# Radio.net
KiCad netlist of a schematic drawn in Altium Designer
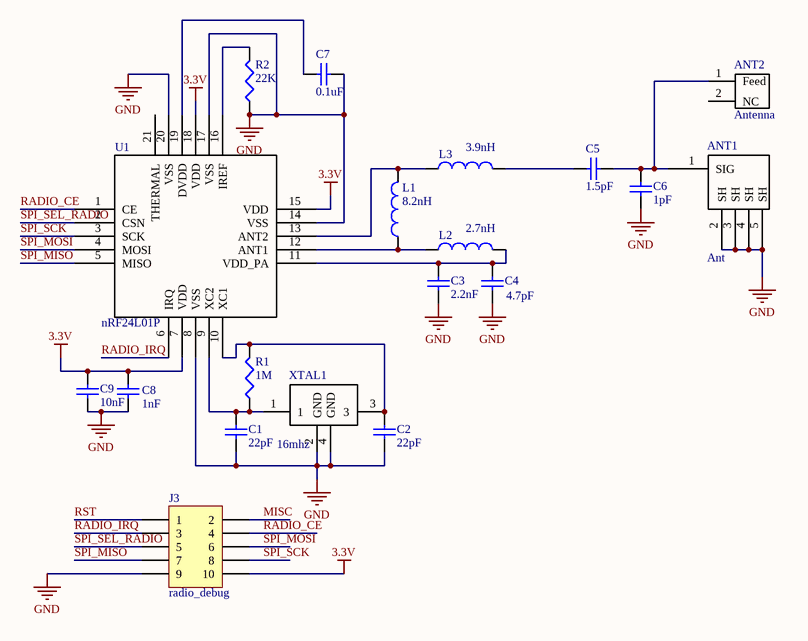
[diagram p0: Radio.SchDoc]

(export (version "E")
  (design (tool "Eeschema 10.0.6"))
  (components
    (comp (ref "ANT1") (value "Ant") (footprint "AntennaSMA") (libsource (lib "mrone") (part "AntennaConn")))
    (comp (ref "ANT2") (value "Antenna") (footprint "antenna") (libsource (lib "mrone") (part "Antenna")))
    (comp (ref "C1")
      (value "22pF")
      (footprint "CAPC1005L")
      (description "Capacitor (Semiconductor SIM Model)")
      (fields (field (name "Comment") "Cap Semi") (field (name "PUBLISHER") "Altium Limited"))
      (libsource (lib "Miscellaneous Devices") (part "Cap Semi"))
    )
    (comp (ref "C2")
      (value "22pF")
      (footprint "CAPC1005L")
      (description "Capacitor (Semiconductor SIM Model)")
      (fields (field (name "Comment") "Cap Semi") (field (name "PUBLISHER") "Altium Limited"))
      (libsource (lib "Miscellaneous Devices") (part "Cap Semi"))
    )
    (comp (ref "C3")
      (value "2.2nF")
      (footprint "CAPC1005L")
      (description "Capacitor (Semiconductor SIM Model)")
      (fields (field (name "Comment") "Cap Semi") (field (name "PUBLISHER") "Altium Limited"))
      (libsource (lib "Miscellaneous Devices") (part "Cap Semi"))
    )
    (comp (ref "C4")
      (value "4.7pF")
      (footprint "CAPC1005L")
      (description "Capacitor (Semiconductor SIM Model)")
      (fields (field (name "Comment") "Cap Semi") (field (name "PUBLISHER") "Altium Limited"))
      (libsource (lib "Miscellaneous Devices") (part "Cap Semi"))
    )
    (comp (ref "C5")
      (value "1.5pF")
      (footprint "CAPC1005L")
      (description "Capacitor (Semiconductor SIM Model)")
      (fields (field (name "Comment") "Cap Semi") (field (name "PUBLISHER") "Altium Limited"))
      (libsource (lib "Miscellaneous Devices") (part "Cap Semi"))
    )
    (comp (ref "C6")
      (value "1pF")
      (footprint "CAPC1005L")
      (description "Capacitor (Semiconductor SIM Model)")
      (fields (field (name "Comment") "Cap Semi") (field (name "PUBLISHER") "Altium Limited"))
      (libsource (lib "Miscellaneous Devices") (part "Cap Semi"))
    )
    (comp (ref "C7")
      (value "0.1uF")
      (footprint "CAPC1005L")
      (description "Capacitor (Semiconductor SIM Model)")
      (fields (field (name "Comment") "Cap Semi") (field (name "PUBLISHER") "Altium Limited"))
      (libsource (lib "Miscellaneous Devices") (part "Cap Semi"))
    )
    (comp (ref "C8")
      (value "1nF")
      (footprint "CAPC1005L")
      (description "Capacitor (Semiconductor SIM Model)")
      (fields (field (name "Comment") "Cap Semi") (field (name "PUBLISHER") "Altium Limited"))
      (libsource (lib "Miscellaneous Devices") (part "Cap Semi"))
    )
    (comp (ref "C9")
      (value "10nF")
      (footprint "CAPC1005L")
      (description "Capacitor (Semiconductor SIM Model)")
      (fields (field (name "Comment") "Cap Semi") (field (name "PUBLISHER") "Altium Limited"))
      (libsource (lib "Miscellaneous Devices") (part "Cap Semi"))
    )
    (comp (ref "J3")
      (value "radio_debug")
      (footprint "HDR2X5")
      (description "Header, 5-Pin, Dual row")
      (fields (field (name "PUBLISHER") "Altium Limited"))
      (libsource (lib "Miscellaneous Connectors") (part "Header 5X2"))
    )
    (comp (ref "L1")
      (value "8.2nH")
      (footprint "INDC1005AL")
      (description "Inductor")
      (fields (field (name "PUBLISHER") "Altium Limited"))
      (libsource (lib "Miscellaneous Devices") (part "Inductor"))
    )
    (comp (ref "L2")
      (value "2.7nH")
      (footprint "INDC1005AL")
      (description "Inductor")
      (fields (field (name "PUBLISHER") "Altium Limited"))
      (libsource (lib "Miscellaneous Devices") (part "Inductor"))
    )
    (comp (ref "L3")
      (value "3.9nH")
      (footprint "INDC1005AL")
      (description "Inductor")
      (fields (field (name "PUBLISHER") "Altium Limited"))
      (libsource (lib "Miscellaneous Devices") (part "Inductor"))
    )
    (comp (ref "R1")
      (value "1M")
      (footprint "RESC1608L")
      (description "Resistor")
      (fields (field (name "Comment") "Res3") (field (name "PUBLISHER") "Altium Limited"))
      (libsource (lib "Miscellaneous Devices") (part "Res3"))
    )
    (comp (ref "R2")
      (value "22K")
      (footprint "RESC1608L")
      (description "Resistor")
      (fields (field (name "Comment") "Res3") (field (name "PUBLISHER") "Altium Limited"))
      (libsource (lib "Miscellaneous Devices") (part "Res3"))
    )
    (comp (ref "U1")
      (value "nRF24L01P")
      (footprint "QFN-20")
      (libsource (lib "mrone") (part "radio-nRF24L01P"))
    )
    (comp (ref "XTAL1")
      (value "16mhz")
      (footprint "RadioCrystal")
      (fields (field (name "Comment") "RADIO CRYSTAL"))
      (libsource (lib "Schematic Components") (part "RadioCrystal"))
    )
  )
  (nets
    (net (code "1") (name "/MISC") (class "Default")
      (node (ref "J3") (pin "2") (pinfunction "2_2") (pintype "passive"))
    )
    (net (code "2") (name "/RADIO_CE") (class "Default")
      (node (ref "J3") (pin "4") (pinfunction "4_4") (pintype "passive"))
      (node (ref "U1") (pin "1") (pinfunction "CE_1") (pintype "passive"))
    )
    (net (code "3") (name "/RADIO_IRQ") (class "Default")
      (node (ref "J3") (pin "3") (pinfunction "3_3") (pintype "passive"))
      (node (ref "U1") (pin "6") (pinfunction "IRQ_6") (pintype "passive"))
    )
    (net (code "4") (name "/RST") (class "Default")
      (node (ref "J3") (pin "1") (pinfunction "1_1") (pintype "passive"))
    )
    (net (code "5") (name "/SPI_MISO") (class "Default")
      (node (ref "J3") (pin "7") (pinfunction "7_7") (pintype "passive"))
      (node (ref "U1") (pin "5") (pinfunction "MISO_5") (pintype "passive"))
    )
    (net (code "6") (name "/SPI_MOSI") (class "Default")
      (node (ref "J3") (pin "6") (pinfunction "6_6") (pintype "passive"))
      (node (ref "U1") (pin "4") (pinfunction "MOSI_4") (pintype "passive"))
    )
    (net (code "7") (name "/SPI_SCK") (class "Default")
      (node (ref "J3") (pin "8") (pinfunction "8_8") (pintype "passive"))
      (node (ref "U1") (pin "3") (pinfunction "SCK_3") (pintype "passive"))
    )
    (net (code "8") (name "/SPI_SEL_RADIO") (class "Default")
      (node (ref "J3") (pin "5") (pinfunction "5_5") (pintype "passive"))
      (node (ref "U1") (pin "2") (pinfunction "CSN_2") (pintype "passive"))
    )
    (net (code "9") (name "3.3V") (class "Default")
      (node (ref "C8") (pin "2") (pinfunction "2_2") (pintype "passive"))
      (node (ref "C9") (pin "2") (pinfunction "2_2") (pintype "passive"))
      (node (ref "J3") (pin "10") (pinfunction "10_10") (pintype "passive"))
      (node (ref "U1") (pin "15") (pinfunction "VDD_15") (pintype "passive"))
      (node (ref "U1") (pin "18") (pinfunction "VDD_18") (pintype "passive"))
      (node (ref "U1") (pin "7") (pinfunction "VDD_7") (pintype "passive"))
    )
    (net (code "10") (name "GND") (class "Default")
      (node (ref "ANT1") (pin "2") (pinfunction "SH_2") (pintype "passive"))
      (node (ref "ANT1") (pin "3") (pinfunction "SH_3") (pintype "passive"))
      (node (ref "ANT1") (pin "4") (pinfunction "SH_4") (pintype "passive"))
      (node (ref "ANT1") (pin "5") (pinfunction "SH_5") (pintype "passive"))
      (node (ref "C1") (pin "1") (pinfunction "1_1") (pintype "passive"))
      (node (ref "C2") (pin "1") (pinfunction "1_1") (pintype "passive"))
      (node (ref "C3") (pin "1") (pinfunction "1_1") (pintype "passive"))
      (node (ref "C4") (pin "1") (pinfunction "1_1") (pintype "passive"))
      (node (ref "C6") (pin "1") (pinfunction "1_1") (pintype "passive"))
      (node (ref "C7") (pin "1") (pinfunction "1_1") (pintype "passive"))
      (node (ref "C8") (pin "1") (pinfunction "1_1") (pintype "passive"))
      (node (ref "C9") (pin "1") (pinfunction "1_1") (pintype "passive"))
      (node (ref "J3") (pin "9") (pinfunction "9_9") (pintype "passive"))
      (node (ref "R2") (pin "1") (pinfunction "1_1") (pintype "passive"))
      (node (ref "U1") (pin "14") (pinfunction "VSS_14") (pintype "passive"))
      (node (ref "U1") (pin "17") (pinfunction "VSS_17") (pintype "passive"))
      (node (ref "U1") (pin "20") (pinfunction "VSS_20") (pintype "passive"))
      (node (ref "U1") (pin "8") (pinfunction "VSS_8") (pintype "passive"))
      (node (ref "XTAL1") (pin "2") (pinfunction "GND_2") (pintype "passive"))
      (node (ref "XTAL1") (pin "4") (pinfunction "GND_4") (pintype "passive"))
    )
    (net (code "11") (name "Net-(ANT1-SIG)") (class "Default")
      (node (ref "ANT1") (pin "1") (pinfunction "SIG_1") (pintype "passive"))
      (node (ref "ANT2") (pin "1") (pinfunction "Feed_1") (pintype "passive"))
      (node (ref "C5") (pin "1") (pinfunction "1_1") (pintype "passive"))
      (node (ref "C6") (pin "2") (pinfunction "2_2") (pintype "passive"))
    )
    (net (code "12") (name "Net-(C5-Pad2)") (class "Default")
      (node (ref "C5") (pin "2") (pinfunction "2_2") (pintype "passive"))
      (node (ref "L3") (pin "2") (pinfunction "2_2") (pintype "passive"))
    )
    (net (code "13") (name "Net-(U1-ANT1)") (class "Default")
      (node (ref "L1") (pin "1") (pinfunction "1_1") (pintype "passive"))
      (node (ref "L2") (pin "1") (pinfunction "1_1") (pintype "passive"))
      (node (ref "U1") (pin "12") (pinfunction "ANT1_12") (pintype "passive"))
    )
    (net (code "14") (name "Net-(U1-ANT2)") (class "Default")
      (node (ref "L1") (pin "2") (pinfunction "2_2") (pintype "passive"))
      (node (ref "L3") (pin "1") (pinfunction "1_1") (pintype "passive"))
      (node (ref "U1") (pin "13") (pinfunction "ANT2_13") (pintype "passive"))
    )
    (net (code "15") (name "Net-(U1-DVDD)") (class "Default")
      (node (ref "C7") (pin "2") (pinfunction "2_2") (pintype "passive"))
      (node (ref "U1") (pin "19") (pinfunction "DVDD_19") (pintype "passive"))
    )
    (net (code "16") (name "Net-(U1-IREF)") (class "Default")
      (node (ref "R2") (pin "2") (pinfunction "2_2") (pintype "passive"))
      (node (ref "U1") (pin "16") (pinfunction "IREF_16") (pintype "passive"))
    )
    (net (code "17") (name "Net-(U1-VDD_PA)") (class "Default")
      (node (ref "C3") (pin "2") (pinfunction "2_2") (pintype "passive"))
      (node (ref "C4") (pin "2") (pinfunction "2_2") (pintype "passive"))
      (node (ref "L2") (pin "2") (pinfunction "2_2") (pintype "passive"))
      (node (ref "U1") (pin "11") (pinfunction "VDD_PA_11") (pintype "passive"))
    )
    (net (code "18") (name "Net-(U1-XC1)") (class "Default")
      (node (ref "C2") (pin "2") (pinfunction "2_2") (pintype "passive"))
      (node (ref "R1") (pin "2") (pinfunction "2_2") (pintype "passive"))
      (node (ref "U1") (pin "10") (pinfunction "XC1_10") (pintype "passive"))
      (node (ref "XTAL1") (pin "3") (pinfunction "3_3") (pintype "passive"))
    )
    (net (code "19") (name "Net-(U1-XC2)") (class "Default")
      (node (ref "C1") (pin "2") (pinfunction "2_2") (pintype "passive"))
      (node (ref "R1") (pin "1") (pinfunction "1_1") (pintype "passive"))
      (node (ref "U1") (pin "9") (pinfunction "XC2_9") (pintype "passive"))
      (node (ref "XTAL1") (pin "1") (pinfunction "1_1") (pintype "passive"))
    )
    (net (code "20") (name "unconnected-(ANT2-NC-Pad2)") (class "Default")
      (node (ref "ANT2") (pin "2") (pinfunction "NC_2") (pintype "passive"))
    )
    (net (code "21") (name "unconnected-(U1-THERMAL-Pad21)") (class "Default")
      (node (ref "U1") (pin "21") (pinfunction "THERMAL_21") (pintype "passive"))
    )
  )
)
